# phantom_sch.net
KiCad netlist of a schematic drawn in EasyEDA
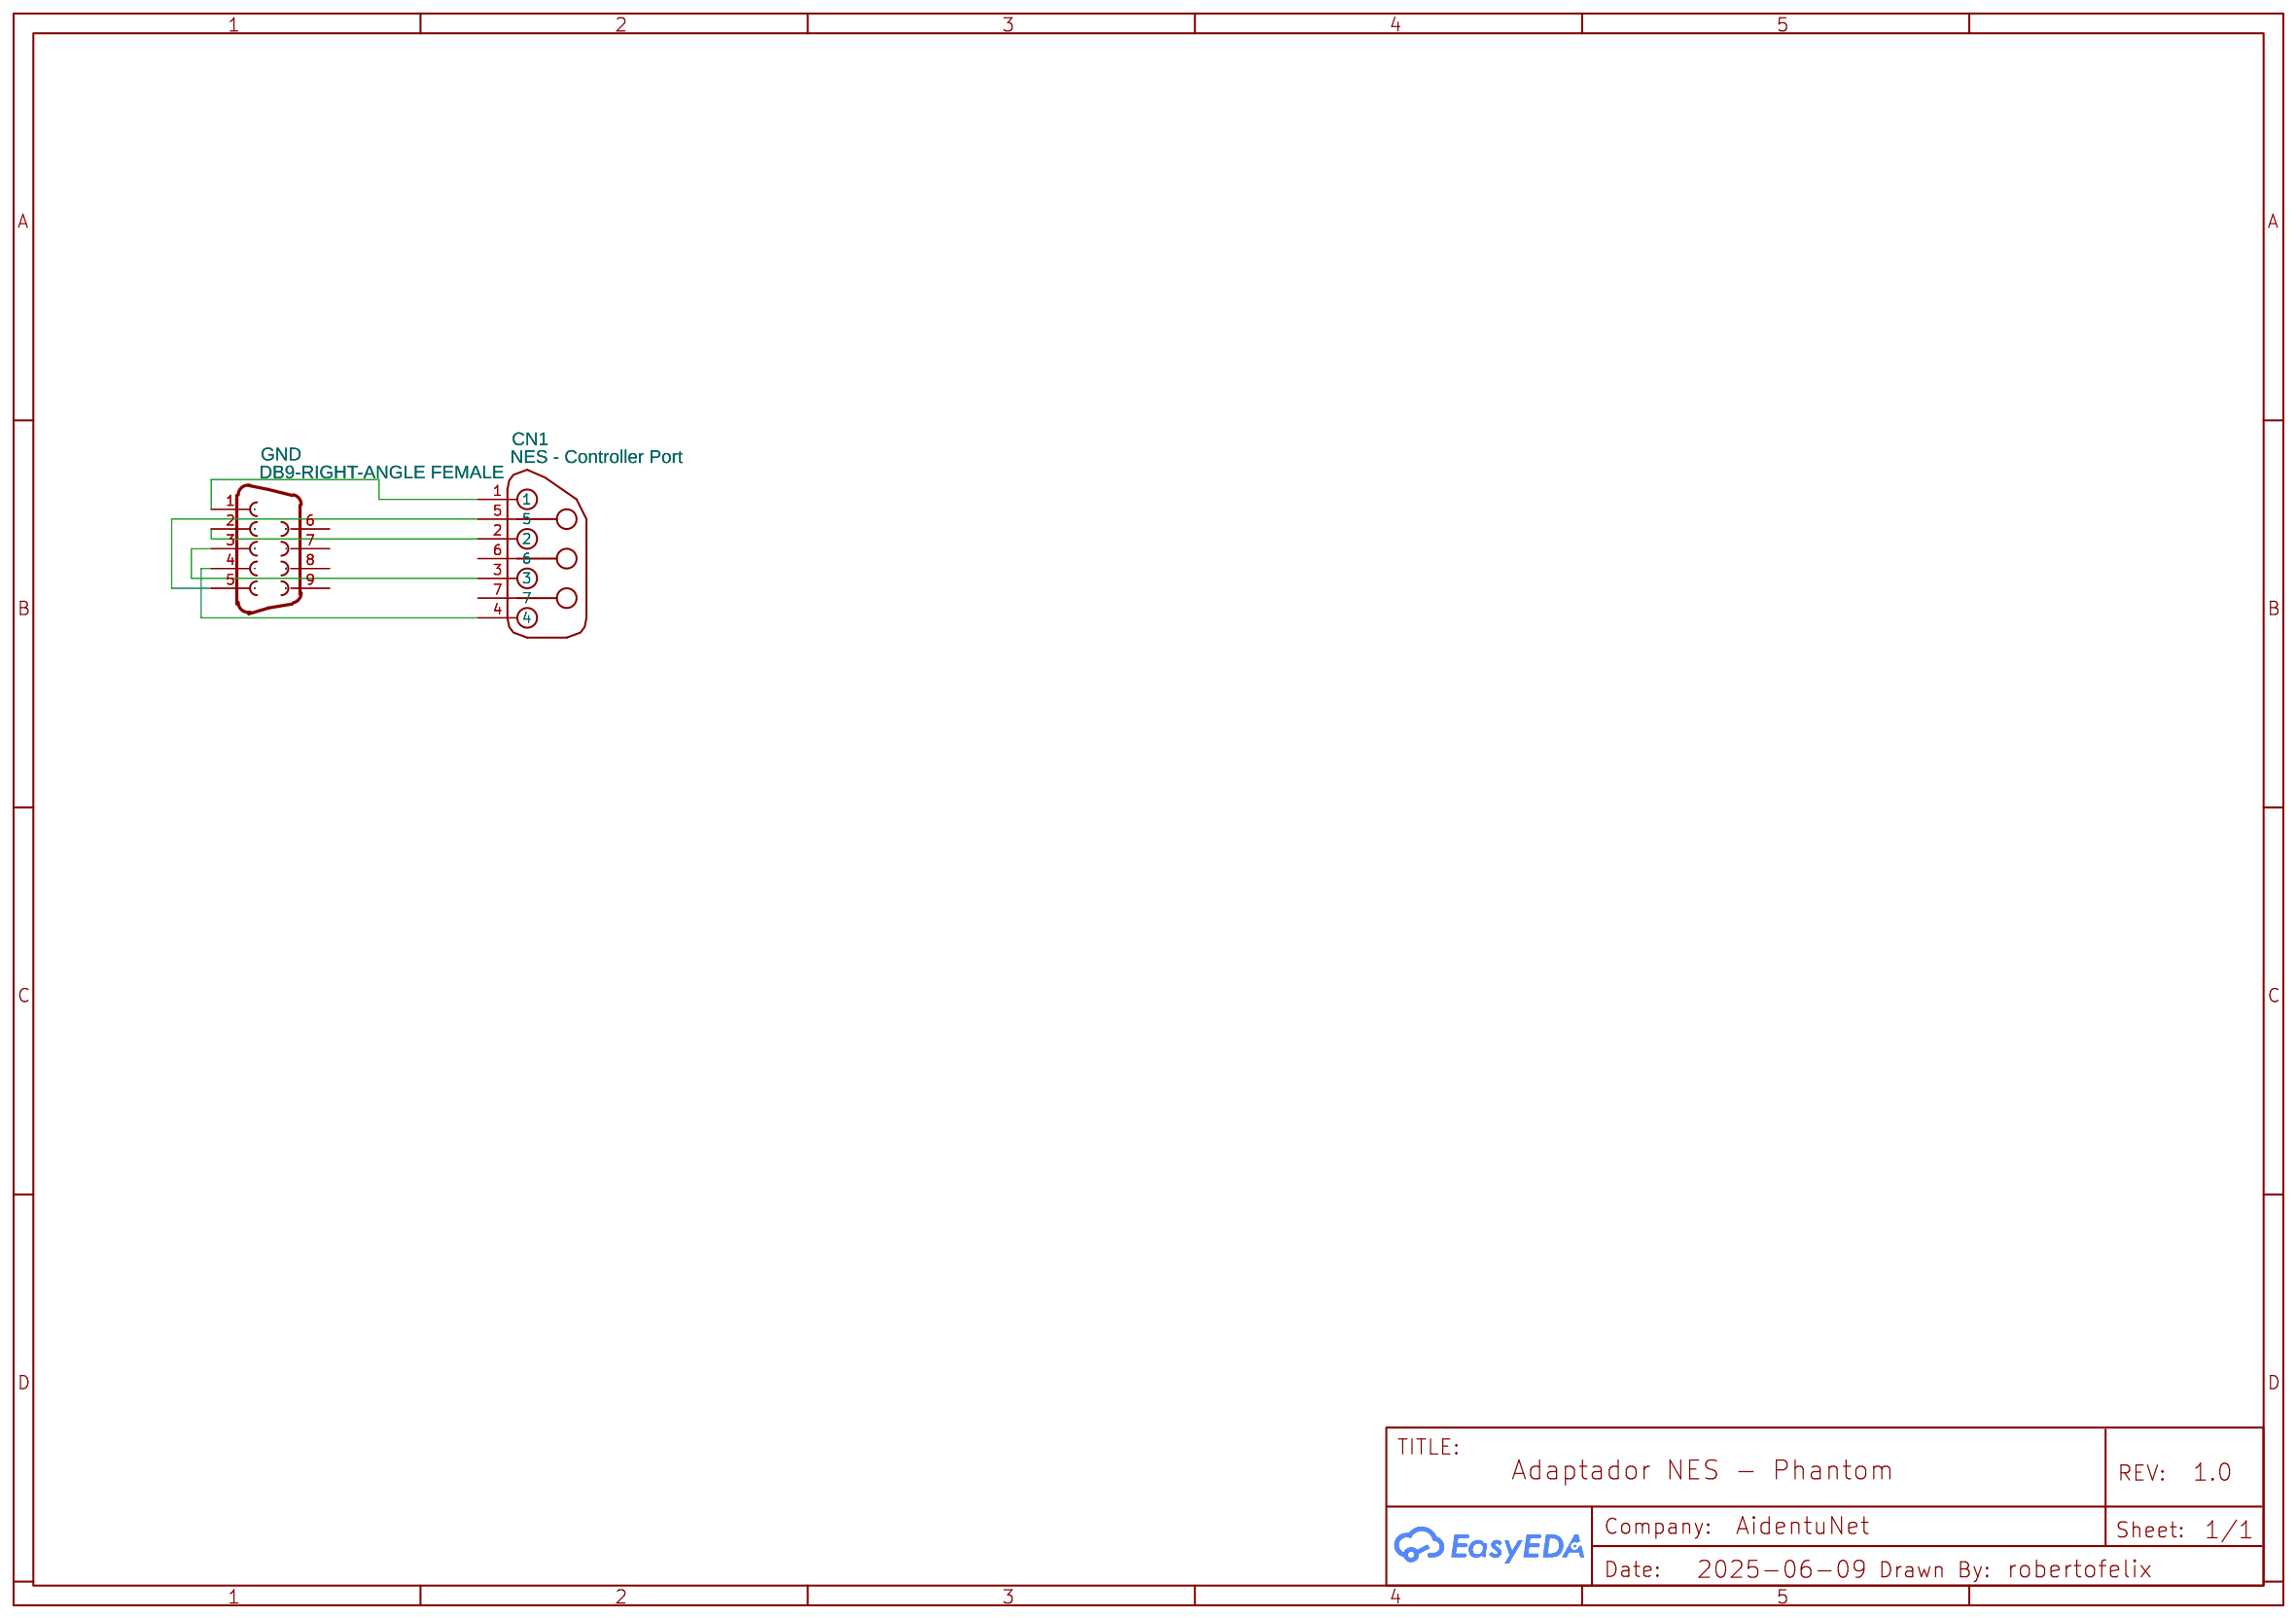
[diagram p0: schematic sheet]

(export (version "E")
  (design (tool "Eeschema 10.0.6"))
  (components
    (comp (ref "CN1") (value "NES - Controller Port") (libsource (lib "") (part "NES - Controller Port")))
    (comp (ref "GND") (value "DB9-RIGHT-ANGLE FEMALE") (libsource (lib "") (part "DB9-RIGHT-ANGLE FEMALE")))
  )
  (nets
    (net (code "1") (name "Net-(CN1-Pad1)") (class "Default")
      (node (ref "CN1") (pin "1") (pinfunction "1_1") (pintype "unspecified"))
      (node (ref "GND") (pin "1") (pinfunction "1_1") (pintype "bidirectional"))
    )
    (net (code "2") (name "Net-(CN1-Pad2)") (class "Default")
      (node (ref "CN1") (pin "2") (pinfunction "2_2") (pintype "unspecified"))
      (node (ref "GND") (pin "2") (pinfunction "2_2") (pintype "bidirectional"))
    )
    (net (code "3") (name "Net-(CN1-Pad3)") (class "Default")
      (node (ref "CN1") (pin "3") (pinfunction "3_3") (pintype "unspecified"))
      (node (ref "GND") (pin "3") (pinfunction "3_3") (pintype "bidirectional"))
    )
    (net (code "4") (name "Net-(CN1-Pad4)") (class "Default")
      (node (ref "CN1") (pin "4") (pinfunction "4_4") (pintype "unspecified"))
      (node (ref "GND") (pin "4") (pinfunction "4_4") (pintype "bidirectional"))
    )
    (net (code "5") (name "Net-(CN1-Pad5)") (class "Default")
      (node (ref "CN1") (pin "5") (pinfunction "5_5") (pintype "unspecified"))
      (node (ref "GND") (pin "5") (pinfunction "5_5") (pintype "bidirectional"))
    )
    (net (code "6") (name "unconnected-(CN1-Pad6)") (class "Default")
      (node (ref "CN1") (pin "6") (pinfunction "6_6") (pintype "unspecified"))
    )
    (net (code "7") (name "unconnected-(CN1-Pad7)") (class "Default")
      (node (ref "CN1") (pin "7") (pinfunction "7_7") (pintype "unspecified"))
    )
    (net (code "8") (name "unconnected-(GND-Pad6)") (class "Default")
      (node (ref "GND") (pin "6") (pinfunction "6_6") (pintype "bidirectional"))
    )
    (net (code "9") (name "unconnected-(GND-Pad7)") (class "Default")
      (node (ref "GND") (pin "7") (pinfunction "7_7") (pintype "bidirectional"))
    )
    (net (code "10") (name "unconnected-(GND-Pad8)") (class "Default")
      (node (ref "GND") (pin "8") (pinfunction "8_8") (pintype "bidirectional"))
    )
    (net (code "11") (name "unconnected-(GND-Pad9)") (class "Default")
      (node (ref "GND") (pin "9") (pinfunction "9_9") (pintype "bidirectional"))
    )
  )
)
